# reLoaD_Motor.net
KiCad netlist of a schematic drawn in EAGLE
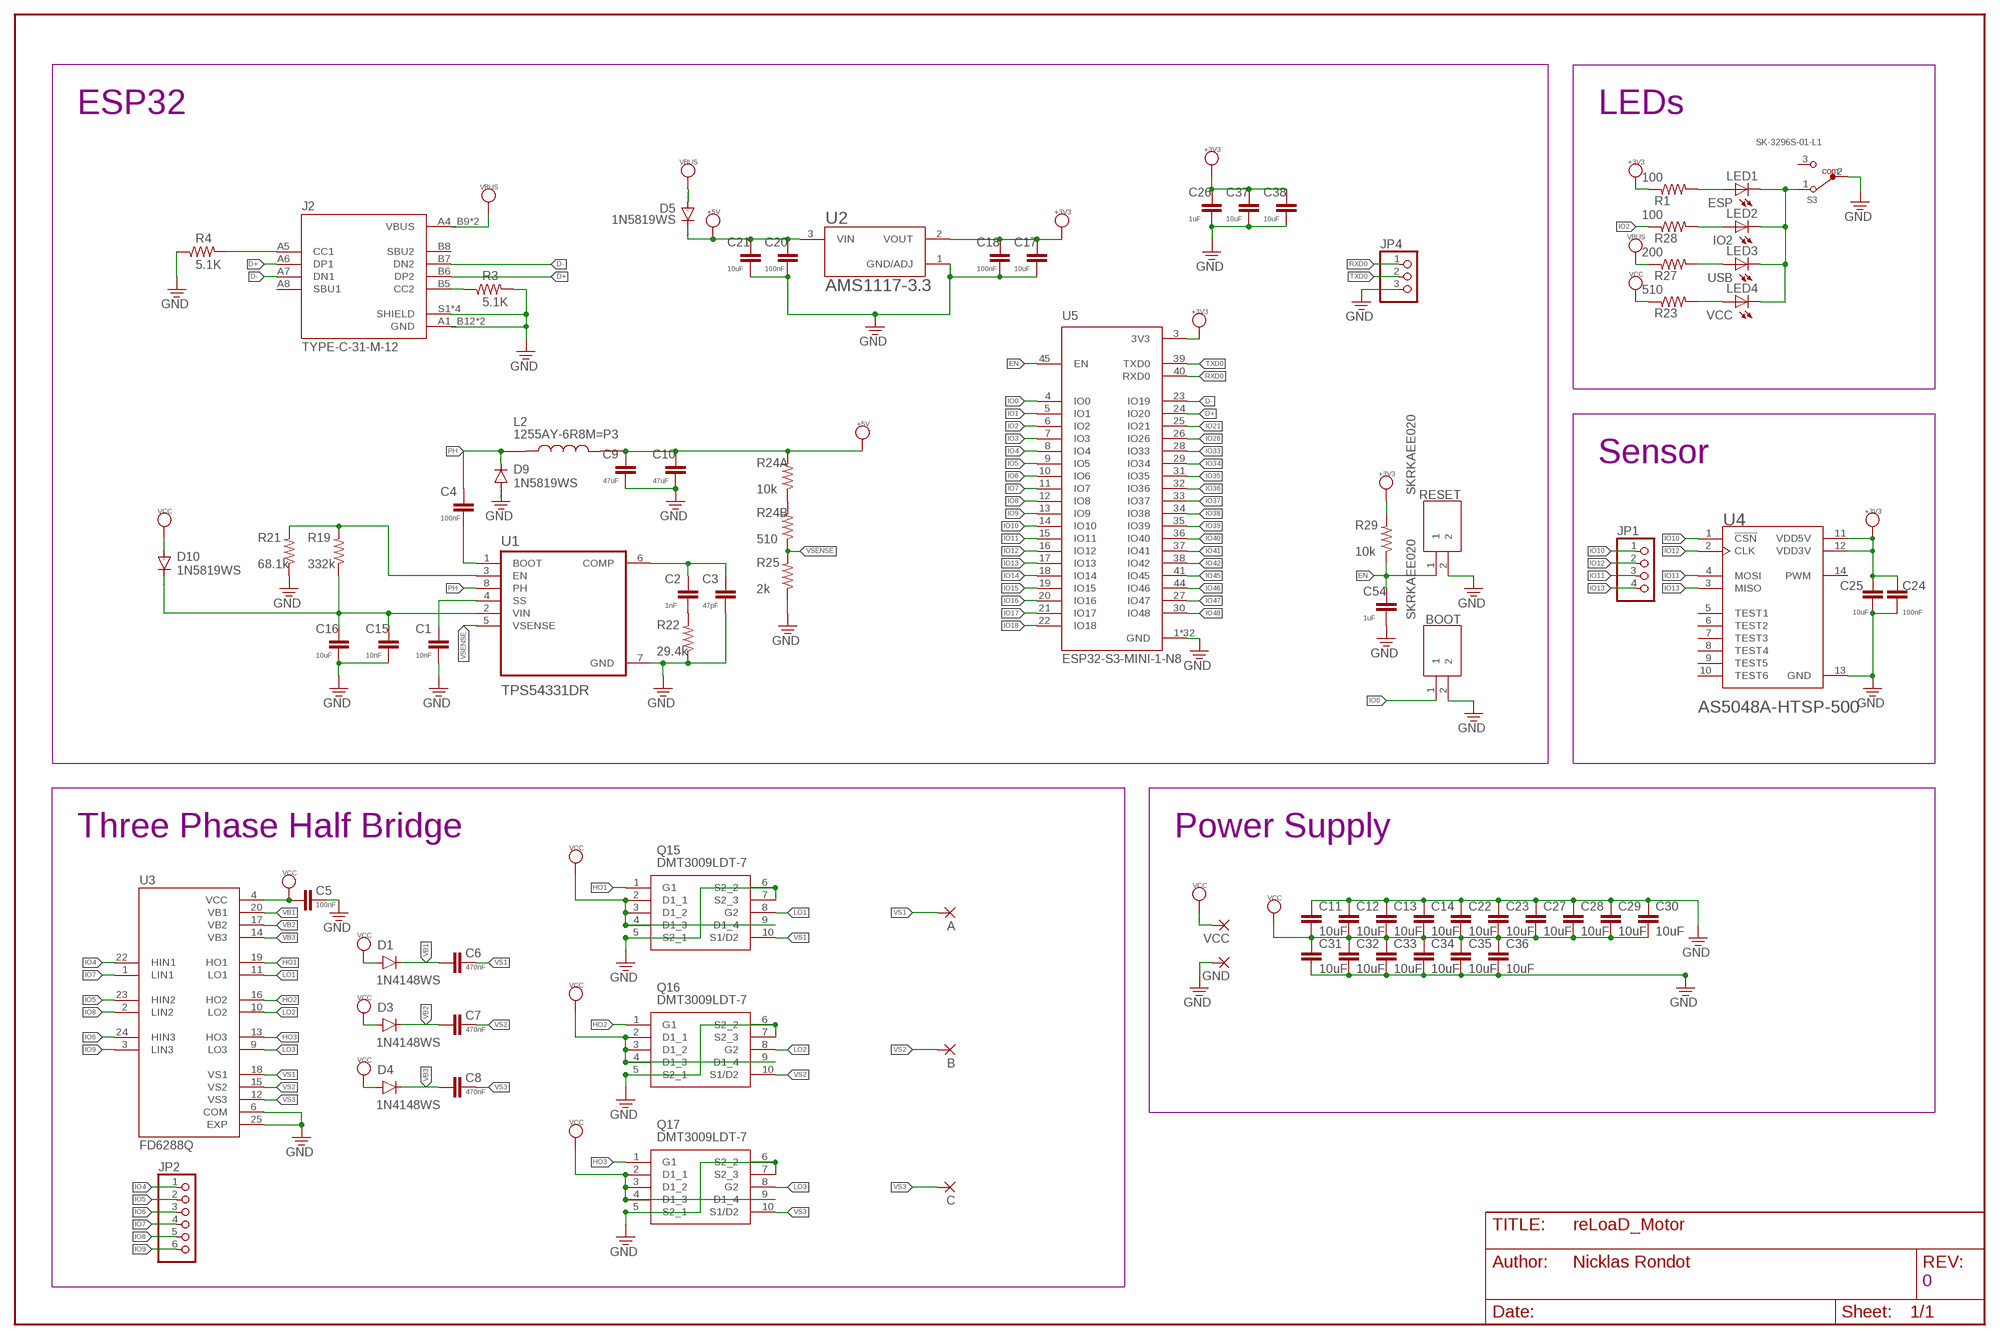
[diagram p0: schematic, sheet 1]

(export (version "E")
  (design (tool "Eeschema 10.0.6"))
  (components
    (comp (ref "A")
      (value "3,81/1,4")
      (footprint "eagle-import:3,81_1,4")
      (libsource (lib "eagle-import") (part "3,81/1,4"))
    )
    (comp (ref "B")
      (value "3,81/1,4")
      (footprint "eagle-import:3,81_1,4")
      (libsource (lib "eagle-import") (part "3,81/1,4"))
    )
    (comp (ref "BOOT")
      (value "SKRKAEE020")
      (footprint "eagle-import:SKRKAEE020")
      (fields (field (name "MOUSER_PART_NUMBER") "688-SKRKAEE020"))
      (libsource (lib "eagle-import") (part "SKRKAEE020"))
    )
    (comp (ref "C")
      (value "3,81/1,4")
      (footprint "eagle-import:3,81_1,4")
      (libsource (lib "eagle-import") (part "3,81/1,4"))
    )
    (comp (ref "C1")
      (value "10nF")
      (footprint "eagle-import:C0603K")
      (libsource (lib "eagle-import") (part "resistor_348_C-EUC0603K"))
    )
    (comp (ref "C2")
      (value "1nF")
      (footprint "eagle-import:C0603K")
      (libsource (lib "eagle-import") (part "resistor_348_C-EUC0603K"))
    )
    (comp (ref "C3")
      (value "47pF")
      (footprint "eagle-import:C0603K")
      (libsource (lib "eagle-import") (part "resistor_348_C-EUC0603K"))
    )
    (comp (ref "C4")
      (value "100nF")
      (footprint "eagle-import:C0603K")
      (libsource (lib "eagle-import") (part "resistor_348_C-EUC0603K"))
    )
    (comp (ref "C5")
      (value "100nF")
      (footprint "eagle-import:C0603K")
      (libsource (lib "eagle-import") (part "resistor_348_C-EUC0603K"))
    )
    (comp (ref "C6")
      (value "470nF")
      (footprint "eagle-import:C0603K")
      (libsource (lib "eagle-import") (part "resistor_348_C-EUC0603K"))
    )
    (comp (ref "C7")
      (value "470nF")
      (footprint "eagle-import:C0603K")
      (libsource (lib "eagle-import") (part "resistor_348_C-EUC0603K"))
    )
    (comp (ref "C8")
      (value "470nF")
      (footprint "eagle-import:C0603K")
      (libsource (lib "eagle-import") (part "resistor_348_C-EUC0603K"))
    )
    (comp (ref "C9")
      (value "47uF")
      (footprint "eagle-import:C0603K")
      (libsource (lib "eagle-import") (part "resistor_348_C-EUC0603K"))
    )
    (comp (ref "C10")
      (value "47uF")
      (footprint "eagle-import:C0603K")
      (libsource (lib "eagle-import") (part "resistor_348_C-EUC0603K"))
    )
    (comp (ref "C11")
      (value "10uF")
      (footprint "eagle-import:C0805K")
      (libsource (lib "eagle-import") (part "C-EUC0805K"))
    )
    (comp (ref "C12")
      (value "10uF")
      (footprint "eagle-import:C0805K")
      (libsource (lib "eagle-import") (part "C-EUC0805K"))
    )
    (comp (ref "C13")
      (value "10uF")
      (footprint "eagle-import:C0805K")
      (libsource (lib "eagle-import") (part "C-EUC0805K"))
    )
    (comp (ref "C14")
      (value "10uF")
      (footprint "eagle-import:C0805K")
      (libsource (lib "eagle-import") (part "C-EUC0805K"))
    )
    (comp (ref "C15")
      (value "10nF")
      (footprint "eagle-import:C0603K")
      (libsource (lib "eagle-import") (part "resistor_348_C-EUC0603K"))
    )
    (comp (ref "C16")
      (value "10uF")
      (footprint "eagle-import:C0603K")
      (libsource (lib "eagle-import") (part "resistor_348_C-EUC0603K"))
    )
    (comp (ref "C17")
      (value "10uF")
      (footprint "eagle-import:C0603K")
      (libsource (lib "eagle-import") (part "resistor_348_C-EUC0603K"))
    )
    (comp (ref "C18")
      (value "100nF")
      (footprint "eagle-import:C0603K")
      (libsource (lib "eagle-import") (part "resistor_348_C-EUC0603K"))
    )
    (comp (ref "C20")
      (value "100nF")
      (footprint "eagle-import:C0603K")
      (libsource (lib "eagle-import") (part "resistor_348_C-EUC0603K"))
    )
    (comp (ref "C21")
      (value "10uF")
      (footprint "eagle-import:C0603K")
      (libsource (lib "eagle-import") (part "resistor_348_C-EUC0603K"))
    )
    (comp (ref "C22")
      (value "10uF")
      (footprint "eagle-import:C0805K")
      (libsource (lib "eagle-import") (part "C-EUC0805K"))
    )
    (comp (ref "C23")
      (value "10uF")
      (footprint "eagle-import:C0805K")
      (libsource (lib "eagle-import") (part "C-EUC0805K"))
    )
    (comp (ref "C24")
      (value "100nF")
      (footprint "eagle-import:C0603K")
      (libsource (lib "eagle-import") (part "resistor_348_C-EUC0603K"))
    )
    (comp (ref "C25")
      (value "10uF")
      (footprint "eagle-import:C0603K")
      (libsource (lib "eagle-import") (part "resistor_348_C-EUC0603K"))
    )
    (comp (ref "C26")
      (value "1uF")
      (footprint "eagle-import:C0603K")
      (libsource (lib "eagle-import") (part "resistor_348_C-EUC0603K"))
    )
    (comp (ref "C27")
      (value "10uF")
      (footprint "eagle-import:C0805K")
      (libsource (lib "eagle-import") (part "C-EUC0805K"))
    )
    (comp (ref "C28")
      (value "10uF")
      (footprint "eagle-import:C0805K")
      (libsource (lib "eagle-import") (part "C-EUC0805K"))
    )
    (comp (ref "C29")
      (value "10uF")
      (footprint "eagle-import:C0805K")
      (libsource (lib "eagle-import") (part "C-EUC0805K"))
    )
    (comp (ref "C30")
      (value "10uF")
      (footprint "eagle-import:C0805K")
      (libsource (lib "eagle-import") (part "C-EUC0805K"))
    )
    (comp (ref "C31")
      (value "10uF")
      (footprint "eagle-import:C0805K")
      (libsource (lib "eagle-import") (part "C-EUC0805K"))
    )
    (comp (ref "C32")
      (value "10uF")
      (footprint "eagle-import:C0805K")
      (libsource (lib "eagle-import") (part "C-EUC0805K"))
    )
    (comp (ref "C33")
      (value "10uF")
      (footprint "eagle-import:C0805K")
      (libsource (lib "eagle-import") (part "C-EUC0805K"))
    )
    (comp (ref "C34")
      (value "10uF")
      (footprint "eagle-import:C0805K")
      (libsource (lib "eagle-import") (part "C-EUC0805K"))
    )
    (comp (ref "C35")
      (value "10uF")
      (footprint "eagle-import:C0805K")
      (libsource (lib "eagle-import") (part "C-EUC0805K"))
    )
    (comp (ref "C36")
      (value "10uF")
      (footprint "eagle-import:C0805K")
      (libsource (lib "eagle-import") (part "C-EUC0805K"))
    )
    (comp (ref "C37")
      (value "10uF")
      (footprint "eagle-import:C0603K")
      (libsource (lib "eagle-import") (part "resistor_348_C-EUC0603K"))
    )
    (comp (ref "C38")
      (value "10uF")
      (footprint "eagle-import:C0603K")
      (libsource (lib "eagle-import") (part "resistor_348_C-EUC0603K"))
    )
    (comp (ref "C54")
      (value "1uF")
      (footprint "eagle-import:C0603K")
      (libsource (lib "eagle-import") (part "resistor_348_C-EUC0603K"))
    )
    (comp (ref "D1")
      (value "1N4148WS")
      (footprint "eagle-import:SOD-323")
      (fields
        (field (name "DIGIKEY_PART_NUMBER") "1N4148WSFSTR-ND")
        (field (name "MANUFACTURER") "Diodes Incorporated")
        (field (name "CREATED_BY") "PCBLayout.com")
      )
      (libsource (lib "eagle-import") (part "1N4148WS"))
    )
    (comp (ref "D3")
      (value "1N4148WS")
      (footprint "eagle-import:SOD-323")
      (fields
        (field (name "DIGIKEY_PART_NUMBER") "1N4148WSFSTR-ND")
        (field (name "MANUFACTURER") "Diodes Incorporated")
        (field (name "CREATED_BY") "PCBLayout.com")
      )
      (libsource (lib "eagle-import") (part "1N4148WS"))
    )
    (comp (ref "D4")
      (value "1N4148WS")
      (footprint "eagle-import:SOD-323")
      (fields
        (field (name "DIGIKEY_PART_NUMBER") "1N4148WSFSTR-ND")
        (field (name "MANUFACTURER") "Diodes Incorporated")
        (field (name "CREATED_BY") "PCBLayout.com")
      )
      (libsource (lib "eagle-import") (part "1N4148WS"))
    )
    (comp (ref "D5")
      (value "1N5819WS")
      (footprint "eagle-import:SOD323-W")
      (libsource (lib "eagle-import") (part "DIODE-SOD323-W"))
    )
    (comp (ref "D9")
      (value "1N5819WS")
      (footprint "eagle-import:SOD323-W")
      (libsource (lib "eagle-import") (part "DIODE-SOD323-W"))
    )
    (comp (ref "D10")
      (value "1N5819WS")
      (footprint "eagle-import:SOD323-W")
      (libsource (lib "eagle-import") (part "DIODE-SOD323-W"))
    )
    (comp (ref "GND")
      (value "3,81/1,4")
      (footprint "eagle-import:3,81_1,4")
      (libsource (lib "eagle-import") (part "3,81/1,4"))
    )
    (comp (ref "J2")
      (value "TYPE-C-31-M-12")
      (footprint "eagle-import:HRO_TYPE-C-31-M-12")
      (fields (field (name "MF") "HRO Electronics Co., Ltd."))
      (libsource (lib "eagle-import") (part "TYPE-C-31-M-12"))
    )
    (comp (ref "JP1")
      (value "PINHD-1X4")
      (footprint "eagle-import:1X04")
      (libsource (lib "eagle-import") (part "PINHD-1X4"))
    )
    (comp (ref "JP2")
      (value "PINHD-1X6")
      (footprint "eagle-import:1X06")
      (libsource (lib "eagle-import") (part "PINHD-1X6"))
    )
    (comp (ref "JP4")
      (value "PINHD-1X3")
      (footprint "eagle-import:1X03")
      (libsource (lib "eagle-import") (part "PINHD-1X3"))
    )
    (comp (ref "L2")
      (value "1255AY-6R8M=P3")
      (footprint "eagle-import:IND_1255AY-6R8M=P3")
      (fields (field (name "MF") "Murata Electronics"))
      (libsource (lib "eagle-import") (part "1255AY-6R8M=P3"))
    )
    (comp (ref "LED1")
      (value "ESP")
      (footprint "eagle-import:CHIPLED_0805")
      (libsource (lib "eagle-import") (part "LEDCHIPLED_0805"))
    )
    (comp (ref "LED2")
      (value "IO2")
      (footprint "eagle-import:CHIPLED_0805")
      (libsource (lib "eagle-import") (part "LEDCHIPLED_0805"))
    )
    (comp (ref "LED3")
      (value "USB")
      (footprint "eagle-import:CHIPLED_0805")
      (libsource (lib "eagle-import") (part "LEDCHIPLED_0805"))
    )
    (comp (ref "LED4")
      (value "VCC")
      (footprint "eagle-import:CHIPLED_0805")
      (libsource (lib "eagle-import") (part "LEDCHIPLED_0805"))
    )
    (comp (ref "Q15")
      (value "DMT3009LDT-7")
      (footprint "eagle-import:DMT3009LDT7")
      (fields (field (name "MOUSER_PART_NUMBER") "621-DMT3009LDT-7"))
      (libsource (lib "eagle-import") (part "DMT3009LDT-7"))
    )
    (comp (ref "Q16")
      (value "DMT3009LDT-7")
      (footprint "eagle-import:DMT3009LDT7")
      (fields (field (name "MOUSER_PART_NUMBER") "621-DMT3009LDT-7"))
      (libsource (lib "eagle-import") (part "DMT3009LDT-7"))
    )
    (comp (ref "Q17")
      (value "DMT3009LDT-7")
      (footprint "eagle-import:DMT3009LDT7")
      (fields (field (name "MOUSER_PART_NUMBER") "621-DMT3009LDT-7"))
      (libsource (lib "eagle-import") (part "DMT3009LDT-7"))
    )
    (comp (ref "R1")
      (value "100")
      (footprint "eagle-import:R0603")
      (libsource (lib "eagle-import") (part "R-US_R0603"))
    )
    (comp (ref "R3")
      (value "5.1K")
      (footprint "eagle-import:R0603")
      (libsource (lib "eagle-import") (part "R-US_R0603"))
    )
    (comp (ref "R4")
      (value "5.1K")
      (footprint "eagle-import:R0603")
      (libsource (lib "eagle-import") (part "R-US_R0603"))
    )
    (comp (ref "R19")
      (value "332k")
      (footprint "eagle-import:R0603")
      (libsource (lib "eagle-import") (part "R-US_R0603"))
    )
    (comp (ref "R21")
      (value "68.1k")
      (footprint "eagle-import:R0603")
      (libsource (lib "eagle-import") (part "R-US_R0603"))
    )
    (comp (ref "R22")
      (value "29.4k")
      (footprint "eagle-import:R0603")
      (libsource (lib "eagle-import") (part "R-US_R0603"))
    )
    (comp (ref "R23")
      (value "510")
      (footprint "eagle-import:R0603")
      (libsource (lib "eagle-import") (part "R-US_R0603"))
    )
    (comp (ref "R24A")
      (value "10k")
      (footprint "eagle-import:R0603")
      (libsource (lib "eagle-import") (part "R-US_R0603"))
    )
    (comp (ref "R24B")
      (value "510")
      (footprint "eagle-import:R0603")
      (libsource (lib "eagle-import") (part "R-US_R0603"))
    )
    (comp (ref "R25")
      (value "2k")
      (footprint "eagle-import:R0603")
      (libsource (lib "eagle-import") (part "R-US_R0603"))
    )
    (comp (ref "R27")
      (value "200")
      (footprint "eagle-import:R0603")
      (libsource (lib "eagle-import") (part "R-US_R0603"))
    )
    (comp (ref "R28")
      (value "100")
      (footprint "eagle-import:R0603")
      (libsource (lib "eagle-import") (part "R-US_R0603"))
    )
    (comp (ref "R29")
      (value "10k")
      (footprint "eagle-import:R0603")
      (libsource (lib "eagle-import") (part "R-US_R0603"))
    )
    (comp (ref "RESET")
      (value "SKRKAEE020")
      (footprint "eagle-import:SKRKAEE020")
      (fields (field (name "MOUSER_PART_NUMBER") "688-SKRKAEE020"))
      (libsource (lib "eagle-import") (part "SKRKAEE020"))
    )
    (comp (ref "S3")
      (value "SK-3296S-01-L1")
      (footprint "eagle-import:450404015514")
      (libsource (lib "eagle-import") (part "450404015514"))
    )
    (comp (ref "U1")
      (value "TPS54331DR")
      (footprint "eagle-import:SOIC127P599X175-8N")
      (fields (field (name "MF") "Texas Instruments"))
      (libsource (lib "eagle-import") (part "TPS54331DR"))
    )
    (comp (ref "U2")
      (value "AMS1117-3.3")
      (footprint "eagle-import:SOT229P700X180-4N")
      (fields (field (name "MF") "Advanced Monolithic Systems"))
      (libsource (lib "eagle-import") (part "AMS1117-3.3"))
    )
    (comp (ref "U3")
      (value "FD6288Q")
      (footprint "eagle-import:QFN50P400X400X90-25N")
      (fields (field (name "MF") "Fortior Tech"))
      (libsource (lib "eagle-import") (part "FD6288Q"))
    )
    (comp (ref "U4")
      (value "AS5048A-HTSP-500")
      (footprint "eagle-import:SOP65P640X120-14N")
      (fields (field (name "MF") "ams"))
      (libsource (lib "eagle-import") (part "AS5048A-HTSP-500"))
    )
    (comp (ref "U5")
      (value "ESP32-S3-MINI-1-N8")
      (footprint "eagle-import:XCVR_ESP32-S3-MINI-1-N8")
      (fields (field (name "MF") "Espressif Systems"))
      (libsource (lib "eagle-import") (part "ESP32-S3-MINI-1-N8"))
    )
    (comp (ref "VCC")
      (value "3,81/1,4")
      (footprint "eagle-import:3,81_1,4")
      (libsource (lib "eagle-import") (part "3,81/1,4"))
    )
  )
  (nets
    (net (code "1") (name "+3V3") (class "Default")
      (node (ref "C17") (pin "1") (pinfunction "1_1") (pintype "passive"))
      (node (ref "C18") (pin "1") (pinfunction "1_1") (pintype "passive"))
      (node (ref "C24") (pin "2") (pinfunction "2_2") (pintype "passive"))
      (node (ref "C25") (pin "2") (pinfunction "2_2") (pintype "passive"))
      (node (ref "C26") (pin "1") (pinfunction "1_1") (pintype "passive"))
      (node (ref "C37") (pin "1") (pinfunction "1_1") (pintype "passive"))
      (node (ref "C38") (pin "1") (pinfunction "1_1") (pintype "passive"))
      (node (ref "R1") (pin "1") (pinfunction "1_1") (pintype "passive"))
      (node (ref "R29") (pin "2") (pinfunction "2_2") (pintype "passive"))
      (node (ref "U2") (pin "2") (pinfunction "VOUT_2") (pintype "output"))
      (node (ref "U4") (pin "11") (pinfunction "VDD5V_11") (pintype "power_in"))
      (node (ref "U4") (pin "12") (pinfunction "VDD3V_12") (pintype "power_in"))
      (node (ref "U5") (pin "3") (pinfunction "3V3_3") (pintype "power_in"))
    )
    (net (code "2") (name "+5V") (class "Default")
      (node (ref "C10") (pin "1") (pinfunction "1_1") (pintype "passive"))
      (node (ref "C20") (pin "1") (pinfunction "1_1") (pintype "passive"))
      (node (ref "C21") (pin "1") (pinfunction "1_1") (pintype "passive"))
      (node (ref "C9") (pin "1") (pinfunction "1_1") (pintype "passive"))
      (node (ref "D5") (pin "C") (pinfunction "C_C") (pintype "passive"))
      (node (ref "L2") (pin "2") (pinfunction "2_2") (pintype "passive"))
      (node (ref "R24A") (pin "2") (pinfunction "2_2") (pintype "passive"))
      (node (ref "U2") (pin "3") (pinfunction "VIN_3") (pintype "input"))
    )
    (net (code "3") (name "D+") (class "Default")
      (node (ref "J2") (pin "A6") (pinfunction "DP1_A6") (pintype "bidirectional"))
      (node (ref "J2") (pin "B6") (pinfunction "DP2_B6") (pintype "bidirectional"))
      (node (ref "U5") (pin "24") (pinfunction "IO20_24") (pintype "bidirectional"))
    )
    (net (code "4") (name "D-") (class "Default")
      (node (ref "J2") (pin "A7") (pinfunction "DN1_A7") (pintype "bidirectional"))
      (node (ref "J2") (pin "B7") (pinfunction "DN2_B7") (pintype "bidirectional"))
      (node (ref "U5") (pin "23") (pinfunction "IO19_23") (pintype "bidirectional"))
    )
    (net (code "5") (name "EN") (class "Default")
      (node (ref "C54") (pin "1") (pinfunction "1_1") (pintype "passive"))
      (node (ref "R29") (pin "1") (pinfunction "1_1") (pintype "passive"))
      (node (ref "RESET") (pin "1") (pinfunction "1_1") (pintype "bidirectional"))
      (node (ref "U5") (pin "45") (pinfunction "EN_45") (pintype "input"))
    )
    (net (code "6") (name "GND") (class "Default")
      (node (ref "BOOT") (pin "2") (pinfunction "2_2") (pintype "bidirectional"))
      (node (ref "C1") (pin "2") (pinfunction "2_2") (pintype "passive"))
      (node (ref "C10") (pin "2") (pinfunction "2_2") (pintype "passive"))
      (node (ref "C11") (pin "1") (pinfunction "1_1") (pintype "passive"))
      (node (ref "C12") (pin "1") (pinfunction "1_1") (pintype "passive"))
      (node (ref "C13") (pin "1") (pinfunction "1_1") (pintype "passive"))
      (node (ref "C14") (pin "1") (pinfunction "1_1") (pintype "passive"))
      (node (ref "C15") (pin "2") (pinfunction "2_2") (pintype "passive"))
      (node (ref "C16") (pin "2") (pinfunction "2_2") (pintype "passive"))
      (node (ref "C17") (pin "2") (pinfunction "2_2") (pintype "passive"))
      (node (ref "C18") (pin "2") (pinfunction "2_2") (pintype "passive"))
      (node (ref "C20") (pin "2") (pinfunction "2_2") (pintype "passive"))
      (node (ref "C21") (pin "2") (pinfunction "2_2") (pintype "passive"))
      (node (ref "C22") (pin "1") (pinfunction "1_1") (pintype "passive"))
      (node (ref "C23") (pin "1") (pinfunction "1_1") (pintype "passive"))
      (node (ref "C24") (pin "1") (pinfunction "1_1") (pintype "passive"))
      (node (ref "C25") (pin "1") (pinfunction "1_1") (pintype "passive"))
      (node (ref "C26") (pin "2") (pinfunction "2_2") (pintype "passive"))
      (node (ref "C27") (pin "1") (pinfunction "1_1") (pintype "passive"))
      (node (ref "C28") (pin "1") (pinfunction "1_1") (pintype "passive"))
      (node (ref "C29") (pin "1") (pinfunction "1_1") (pintype "passive"))
      (node (ref "C3") (pin "2") (pinfunction "2_2") (pintype "passive"))
      (node (ref "C30") (pin "1") (pinfunction "1_1") (pintype "passive"))
      (node (ref "C31") (pin "2") (pinfunction "2_2") (pintype "passive"))
      (node (ref "C32") (pin "2") (pinfunction "2_2") (pintype "passive"))
      (node (ref "C33") (pin "2") (pinfunction "2_2") (pintype "passive"))
      (node (ref "C34") (pin "2") (pinfunction "2_2") (pintype "passive"))
      (node (ref "C35") (pin "2") (pinfunction "2_2") (pintype "passive"))
      (node (ref "C36") (pin "2") (pinfunction "2_2") (pintype "passive"))
      (node (ref "C37") (pin "2") (pinfunction "2_2") (pintype "passive"))
      (node (ref "C38") (pin "2") (pinfunction "2_2") (pintype "passive"))
      (node (ref "C5") (pin "1") (pinfunction "1_1") (pintype "passive"))
      (node (ref "C54") (pin "2") (pinfunction "2_2") (pintype "passive"))
      (node (ref "C9") (pin "2") (pinfunction "2_2") (pintype "passive"))
      (node (ref "D9") (pin "A") (pinfunction "A_A") (pintype "passive"))
      (node (ref "GND") (pin "1") (pinfunction "P_1") (pintype "passive"))
      (node (ref "J2") (pin "A1_B12") (pinfunction "GND_A1_B12") (pintype "power_in"))
      (node (ref "J2") (pin "B1_A12") (pinfunction "GND_B1_A12") (pintype "power_in"))
      (node (ref "J2") (pin "S1") (pinfunction "SHIELD_S1") (pintype "passive"))
      (node (ref "J2") (pin "S2") (pinfunction "SHIELD_S2") (pintype "passive"))
      (node (ref "J2") (pin "S3") (pinfunction "SHIELD_S3") (pintype "passive"))
      (node (ref "J2") (pin "S4") (pinfunction "SHIELD_S4") (pintype "passive"))
      (node (ref "JP4") (pin "3") (pinfunction "3_3") (pintype "passive"))
      (node (ref "Q15") (pin "5") (pinfunction "S2_1_5") (pintype "bidirectional"))
      (node (ref "Q15") (pin "6") (pinfunction "S2_2_6") (pintype "bidirectional"))
      (node (ref "Q15") (pin "7") (pinfunction "S2_3_7") (pintype "bidirectional"))
      (node (ref "Q16") (pin "5") (pinfunction "S2_1_5") (pintype "bidirectional"))
      (node (ref "Q16") (pin "6") (pinfunction "S2_2_6") (pintype "bidirectional"))
      (node (ref "Q16") (pin "7") (pinfunction "S2_3_7") (pintype "bidirectional"))
      (node (ref "Q17") (pin "5") (pinfunction "S2_1_5") (pintype "bidirectional"))
      (node (ref "Q17") (pin "6") (pinfunction "S2_2_6") (pintype "bidirectional"))
      (node (ref "Q17") (pin "7") (pinfunction "S2_3_7") (pintype "bidirectional"))
      (node (ref "R21") (pin "1") (pinfunction "1_1") (pintype "passive"))
      (node (ref "R22") (pin "1") (pinfunction "1_1") (pintype "passive"))
      (node (ref "R25") (pin "1") (pinfunction "1_1") (pintype "passive"))
      (node (ref "R3") (pin "2") (pinfunction "2_2") (pintype "passive"))
      (node (ref "R4") (pin "1") (pinfunction "1_1") (pintype "passive"))
      (node (ref "RESET") (pin "2") (pinfunction "2_2") (pintype "bidirectional"))
      (node (ref "S3") (pin "2") (pinfunction "2_2") (pintype "passive"))
      (node (ref "U1") (pin "7") (pinfunction "GND_7") (pintype "power_in"))
      (node (ref "U2") (pin "1") (pinfunction "GND/ADJ_1") (pintype "power_in"))
      (node (ref "U3") (pin "25") (pinfunction "EXP_25") (pintype "power_in"))
      (node (ref "U3") (pin "6") (pinfunction "COM_6") (pintype "power_in"))
      (node (ref "U4") (pin "13") (pinfunction "GND_13") (pintype "passive"))
      (node (ref "U5") (pin "1") (pinfunction "GND_1") (pintype "power_in"))
      (node (ref "U5") (pin "2") (pinfunction "GND_2") (pintype "power_in"))
      (node (ref "U5") (pin "42") (pinfunction "GND_42") (pintype "power_in"))
      (node (ref "U5") (pin "43") (pinfunction "GND_43") (pintype "power_in"))
      (node (ref "U5") (pin "46") (pinfunction "GND_46") (pintype "power_in"))
      (node (ref "U5") (pin "47") (pinfunction "GND_47") (pintype "power_in"))
      (node (ref "U5") (pin "48") (pinfunction "GND_48") (pintype "power_in"))
      (node (ref "U5") (pin "49") (pinfunction "GND_49") (pintype "power_in"))
      (node (ref "U5") (pin "50") (pinfunction "GND_50") (pintype "power_in"))
      (node (ref "U5") (pin "51") (pinfunction "GND_51") (pintype "power_in"))
      (node (ref "U5") (pin "52") (pinfunction "GND_52") (pintype "power_in"))
      (node (ref "U5") (pin "53") (pinfunction "GND_53") (pintype "power_in"))
      (node (ref "U5") (pin "54") (pinfunction "GND_54") (pintype "power_in"))
      (node (ref "U5") (pin "55") (pinfunction "GND_55") (pintype "power_in"))
      (node (ref "U5") (pin "56") (pinfunction "GND_56") (pintype "power_in"))
      (node (ref "U5") (pin "57") (pinfunction "GND_57") (pintype "power_in"))
      (node (ref "U5") (pin "58") (pinfunction "GND_58") (pintype "power_in"))
      (node (ref "U5") (pin "59") (pinfunction "GND_59") (pintype "power_in"))
      (node (ref "U5") (pin "60") (pinfunction "GND_60") (pintype "power_in"))
      (node (ref "U5") (pin "61") (pinfunction "GND_61") (pintype "power_in"))
      (node (ref "U5") (pin "61_1") (pinfunction "GND_61_1") (pintype "power_in"))
      (node (ref "U5") (pin "61_2") (pinfunction "GND_61_2") (pintype "power_in"))
      (node (ref "U5") (pin "61_3") (pinfunction "GND_61_3") (pintype "power_in"))
      (node (ref "U5") (pin "61_4") (pinfunction "GND_61_4") (pintype "power_in"))
      (node (ref "U5") (pin "61_5") (pinfunction "GND_61_5") (pintype "power_in"))
      (node (ref "U5") (pin "61_6") (pinfunction "GND_61_6") (pintype "power_in"))
      (node (ref "U5") (pin "61_7") (pinfunction "GND_61_7") (pintype "power_in"))
      (node (ref "U5") (pin "61_8") (pinfunction "GND_61_8") (pintype "power_in"))
      (node (ref "U5") (pin "62") (pinfunction "GND_62") (pintype "power_in"))
      (node (ref "U5") (pin "63") (pinfunction "GND_63") (pintype "power_in"))
      (node (ref "U5") (pin "64") (pinfunction "GND_64") (pintype "power_in"))
      (node (ref "U5") (pin "65") (pinfunction "GND_65") (pintype "power_in"))
    )
    (net (code "7") (name "HO1") (class "Default")
      (node (ref "Q15") (pin "1") (pinfunction "G1_1") (pintype "bidirectional"))
      (node (ref "U3") (pin "19") (pinfunction "HO1_19") (pintype "output"))
    )
    (net (code "8") (name "HO2") (class "Default")
      (node (ref "Q16") (pin "1") (pinfunction "G1_1") (pintype "bidirectional"))
      (node (ref "U3") (pin "16") (pinfunction "HO2_16") (pintype "output"))
    )
    (net (code "9") (name "HO3") (class "Default")
      (node (ref "Q17") (pin "1") (pinfunction "G1_1") (pintype "bidirectional"))
      (node (ref "U3") (pin "13") (pinfunction "HO3_13") (pintype "output"))
    )
    (net (code "10") (name "IO0") (class "Default")
      (node (ref "BOOT") (pin "1") (pinfunction "1_1") (pintype "bidirectional"))
      (node (ref "U5") (pin "4") (pinfunction "IO0_4") (pintype "bidirectional"))
    )
    (net (code "11") (name "IO1") (class "Default")
      (node (ref "U5") (pin "5") (pinfunction "IO1_5") (pintype "bidirectional"))
    )
    (net (code "12") (name "IO2") (class "Default")
      (node (ref "R28") (pin "1") (pinfunction "1_1") (pintype "passive"))
      (node (ref "U5") (pin "6") (pinfunction "IO2_6") (pintype "bidirectional"))
    )
    (net (code "13") (name "IO3") (class "Default")
      (node (ref "U5") (pin "7") (pinfunction "IO3_7") (pintype "bidirectional"))
    )
    (net (code "14") (name "IO4") (class "Default")
      (node (ref "JP2") (pin "1") (pinfunction "1_1") (pintype "passive"))
      (node (ref "U3") (pin "22") (pinfunction "HIN1_22") (pintype "input"))
      (node (ref "U5") (pin "8") (pinfunction "IO4_8") (pintype "bidirectional"))
    )
    (net (code "15") (name "IO5") (class "Default")
      (node (ref "JP2") (pin "2") (pinfunction "2_2") (pintype "passive"))
      (node (ref "U3") (pin "23") (pinfunction "HIN2_23") (pintype "input"))
      (node (ref "U5") (pin "9") (pinfunction "IO5_9") (pintype "bidirectional"))
    )
    (net (code "16") (name "IO6") (class "Default")
      (node (ref "JP2") (pin "3") (pinfunction "3_3") (pintype "passive"))
      (node (ref "U3") (pin "24") (pinfunction "HIN3_24") (pintype "input"))
      (node (ref "U5") (pin "10") (pinfunction "IO6_10") (pintype "bidirectional"))
    )
    (net (code "17") (name "IO7") (class "Default")
      (node (ref "JP2") (pin "4") (pinfunction "4_4") (pintype "passive"))
      (node (ref "U3") (pin "1") (pinfunction "LIN1_1") (pintype "input"))
      (node (ref "U5") (pin "11") (pinfunction "IO7_11") (pintype "bidirectional"))
    )
    (net (code "18") (name "IO8") (class "Default")
      (node (ref "JP2") (pin "5") (pinfunction "5_5") (pintype "passive"))
      (node (ref "U3") (pin "2") (pinfunction "LIN2_2") (pintype "input"))
      (node (ref "U5") (pin "12") (pinfunction "IO8_12") (pintype "bidirectional"))
    )
    (net (code "19") (name "IO9") (class "Default")
      (node (ref "JP2") (pin "6") (pinfunction "6_6") (pintype "passive"))
      (node (ref "U3") (pin "3") (pinfunction "LIN3_3") (pintype "input"))
      (node (ref "U5") (pin "13") (pinfunction "IO9_13") (pintype "bidirectional"))
    )
    (net (code "20") (name "IO10") (class "Default")
      (node (ref "JP1") (pin "1") (pinfunction "1_1") (pintype "passive"))
      (node (ref "U4") (pin "1") (pinfunction "~{CSN}_1") (pintype "input"))
      (node (ref "U5") (pin "14") (pinfunction "IO10_14") (pintype "bidirectional"))
    )
    (net (code "21") (name "IO11") (class "Default")
      (node (ref "JP1") (pin "3") (pinfunction "3_3") (pintype "passive"))
      (node (ref "U4") (pin "4") (pinfunction "MOSI_4") (pintype "input"))
      (node (ref "U5") (pin "15") (pinfunction "IO11_15") (pintype "bidirectional"))
    )
    (net (code "22") (name "IO12") (class "Default")
      (node (ref "JP1") (pin "2") (pinfunction "2_2") (pintype "passive"))
      (node (ref "U4") (pin "2") (pinfunction "CLK_2") (pintype "input"))
      (node (ref "U5") (pin "16") (pinfunction "IO12_16") (pintype "bidirectional"))
    )
    (net (code "23") (name "IO13") (class "Default")
      (node (ref "JP1") (pin "4") (pinfunction "4_4") (pintype "passive"))
      (node (ref "U4") (pin "3") (pinfunction "MISO_3") (pintype "bidirectional"))
      (node (ref "U5") (pin "17") (pinfunction "IO13_17") (pintype "bidirectional"))
    )
    (net (code "24") (name "IO14") (class "Default")
      (node (ref "U5") (pin "18") (pinfunction "IO14_18") (pintype "bidirectional"))
    )
    (net (code "25") (name "IO15") (class "Default")
      (node (ref "U5") (pin "19") (pinfunction "IO15_19") (pintype "bidirectional"))
    )
    (net (code "26") (name "IO16") (class "Default")
      (node (ref "U5") (pin "20") (pinfunction "IO16_20") (pintype "bidirectional"))
    )
    (net (code "27") (name "IO17") (class "Default")
      (node (ref "U5") (pin "21") (pinfunction "IO17_21") (pintype "bidirectional"))
    )
    (net (code "28") (name "IO18") (class "Default")
      (node (ref "U5") (pin "22") (pinfunction "IO18_22") (pintype "bidirectional"))
    )
    (net (code "29") (name "IO21") (class "Default")
      (node (ref "U5") (pin "25") (pinfunction "IO21_25") (pintype "bidirectional"))
    )
    (net (code "30") (name "IO26") (class "Default")
      (node (ref "U5") (pin "26") (pinfunction "IO26_26") (pintype "bidirectional"))
    )
    (net (code "31") (name "IO33") (class "Default")
      (node (ref "U5") (pin "28") (pinfunction "IO33_28") (pintype "bidirectional"))
    )
    (net (code "32") (name "IO34") (class "Default")
      (node (ref "U5") (pin "29") (pinfunction "IO34_29") (pintype "bidirectional"))
    )
    (net (code "33") (name "IO35") (class "Default")
      (node (ref "U5") (pin "31") (pinfunction "IO35_31") (pintype "bidirectional"))
    )
    (net (code "34") (name "IO36") (class "Default")
      (node (ref "U5") (pin "32") (pinfunction "IO36_32") (pintype "bidirectional"))
    )
    (net (code "35") (name "IO37") (class "Default")
      (node (ref "U5") (pin "33") (pinfunction "IO37_33") (pintype "bidirectional"))
    )
    (net (code "36") (name "IO38") (class "Default")
      (node (ref "U5") (pin "34") (pinfunction "IO38_34") (pintype "bidirectional"))
    )
    (net (code "37") (name "IO39") (class "Default")
      (node (ref "U5") (pin "35") (pinfunction "IO39_35") (pintype "bidirectional"))
    )
    (net (code "38") (name "IO40") (class "Default")
      (node (ref "U5") (pin "36") (pinfunction "IO40_36") (pintype "bidirectional"))
    )
    (net (code "39") (name "IO41") (class "Default")
      (node (ref "U5") (pin "37") (pinfunction "IO41_37") (pintype "bidirectional"))
    )
    (net (code "40") (name "IO42") (class "Default")
      (node (ref "U5") (pin "38") (pinfunction "IO42_38") (pintype "bidirectional"))
    )
    (net (code "41") (name "IO45") (class "Default")
      (node (ref "U5") (pin "41") (pinfunction "IO45_41") (pintype "bidirectional"))
    )
    (net (code "42") (name "IO46") (class "Default")
      (node (ref "U5") (pin "44") (pinfunction "IO46_44") (pintype "bidirectional"))
    )
    (net (code "43") (name "IO47") (class "Default")
      (node (ref "U5") (pin "27") (pinfunction "IO47_27") (pintype "bidirectional"))
    )
    (net (code "44") (name "IO48") (class "Default")
      (node (ref "U5") (pin "30") (pinfunction "IO48_30") (pintype "bidirectional"))
    )
    (net (code "45") (name "LO1") (class "Default")
      (node (ref "Q15") (pin "8") (pinfunction "G2_8") (pintype "bidirectional"))
      (node (ref "U3") (pin "11") (pinfunction "LO1_11") (pintype "output"))
    )
    (net (code "46") (name "LO2") (class "Default")
      (node (ref "Q16") (pin "8") (pinfunction "G2_8") (pintype "bidirectional"))
      (node (ref "U3") (pin "10") (pinfunction "LO2_10") (pintype "output"))
    )
    (net (code "47") (name "LO3") (class "Default")
      (node (ref "Q17") (pin "8") (pinfunction "G2_8") (pintype "bidirectional"))
      (node (ref "U3") (pin "9") (pinfunction "LO3_9") (pintype "output"))
    )
    (net (code "48") (name "Net-(C2-Pad2)") (class "Default")
      (node (ref "C2") (pin "2") (pinfunction "2_2") (pintype "passive"))
      (node (ref "R22") (pin "2") (pinfunction "2_2") (pintype "passive"))
    )
    (net (code "49") (name "Net-(J2-CC1)") (class "Default")
      (node (ref "J2") (pin "A5") (pinfunction "CC1_A5") (pintype "bidirectional"))
      (node (ref "R4") (pin "2") (pinfunction "2_2") (pintype "passive"))
    )
    (net (code "50") (name "Net-(J2-CC2)") (class "Default")
      (node (ref "J2") (pin "B5") (pinfunction "CC2_B5") (pintype "bidirectional"))
      (node (ref "R3") (pin "1") (pinfunction "1_1") (pintype "passive"))
    )
    (net (code "51") (name "Net-(LED1-PadA)") (class "Default")
      (node (ref "LED1") (pin "A") (pinfunction "A_A") (pintype "passive"))
      (node (ref "R1") (pin "2") (pinfunction "2_2") (pintype "passive"))
    )
    (net (code "52") (name "Net-(LED1-PadC)") (class "Default")
      (node (ref "LED1") (pin "C") (pinfunction "C_C") (pintype "passive"))
      (node (ref "LED2") (pin "C") (pinfunction "C_C") (pintype "passive"))
      (node (ref "LED3") (pin "C") (pinfunction "C_C") (pintype "passive"))
      (node (ref "LED4") (pin "C") (pinfunction "C_C") (pintype "passive"))
      (node (ref "S3") (pin "1") (pinfunction "1_1") (pintype "passive"))
    )
    (net (code "53") (name "Net-(LED2-PadA)") (class "Default")
      (node (ref "LED2") (pin "A") (pinfunction "A_A") (pintype "passive"))
      (node (ref "R28") (pin "2") (pinfunction "2_2") (pintype "passive"))
    )
    (net (code "54") (name "Net-(LED3-PadA)") (class "Default")
      (node (ref "LED3") (pin "A") (pinfunction "A_A") (pintype "passive"))
      (node (ref "R27") (pin "2") (pinfunction "2_2") (pintype "passive"))
    )
    (net (code "55") (name "Net-(LED4-PadA)") (class "Default")
      (node (ref "LED4") (pin "A") (pinfunction "A_A") (pintype "passive"))
      (node (ref "R23") (pin "2") (pinfunction "2_2") (pintype "passive"))
    )
    (net (code "56") (name "Net-(R24A-Pad1)") (class "Default")
      (node (ref "R24A") (pin "1") (pinfunction "1_1") (pintype "passive"))
      (node (ref "R24B") (pin "2") (pinfunction "2_2") (pintype "passive"))
    )
    (net (code "57") (name "Net-(U1-BOOT)") (class "Default")
      (node (ref "C4") (pin "2") (pinfunction "2_2") (pintype "passive"))
      (node (ref "U1") (pin "1") (pinfunction "BOOT_1") (pintype "input"))
    )
    (net (code "58") (name "Net-(U1-COMP)") (class "Default")
      (node (ref "C2") (pin "1") (pinfunction "1_1") (pintype "passive"))
      (node (ref "C3") (pin "1") (pinfunction "1_1") (pintype "passive"))
      (node (ref "U1") (pin "6") (pinfunction "COMP_6") (pintype "output"))
    )
    (net (code "59") (name "Net-(U1-EN)") (class "Default")
      (node (ref "R19") (pin "2") (pinfunction "2_2") (pintype "passive"))
      (node (ref "R21") (pin "2") (pinfunction "2_2") (pintype "passive"))
      (node (ref "U1") (pin "3") (pinfunction "EN_3") (pintype "input"))
    )
    (net (code "60") (name "Net-(U1-SS)") (class "Default")
      (node (ref "C1") (pin "1") (pinfunction "1_1") (pintype "passive"))
      (node (ref "U1") (pin "4") (pinfunction "SS_4") (pintype "input"))
    )
    (net (code "61") (name "Net-(U1-VIN)") (class "Default")
      (node (ref "C15") (pin "1") (pinfunction "1_1") (pintype "passive"))
      (node (ref "C16") (pin "1") (pinfunction "1_1") (pintype "passive"))
      (node (ref "D10") (pin "C") (pinfunction "C_C") (pintype "passive"))
      (node (ref "R19") (pin "1") (pinfunction "1_1") (pintype "passive"))
      (node (ref "U1") (pin "2") (pinfunction "VIN_2") (pintype "input"))
    )
    (net (code "62") (name "PH") (class "Default")
      (node (ref "C4") (pin "1") (pinfunction "1_1") (pintype "passive"))
      (node (ref "D9") (pin "C") (pinfunction "C_C") (pintype "passive"))
      (node (ref "L2") (pin "1") (pinfunction "1_1") (pintype "passive"))
      (node (ref "U1") (pin "8") (pinfunction "PH_8") (pintype "input"))
    )
    (net (code "63") (name "RXD0") (class "Default")
      (node (ref "JP4") (pin "1") (pinfunction "1_1") (pintype "passive"))
      (node (ref "U5") (pin "40") (pinfunction "RXD0_40") (pintype "bidirectional"))
    )
    (net (code "64") (name "TXD0") (class "Default")
      (node (ref "JP4") (pin "2") (pinfunction "2_2") (pintype "passive"))
      (node (ref "U5") (pin "39") (pinfunction "TXD0_39") (pintype "bidirectional"))
    )
    (net (code "65") (name "VB1") (class "Default")
      (node (ref "C6") (pin "1") (pinfunction "1_1") (pintype "passive"))
      (node (ref "D1") (pin "C") (pinfunction "C_C") (pintype "passive"))
      (node (ref "U3") (pin "20") (pinfunction "VB1_20") (pintype "power_in"))
    )
    (net (code "66") (name "VB2") (class "Default")
      (node (ref "C7") (pin "1") (pinfunction "1_1") (pintype "passive"))
      (node (ref "D3") (pin "C") (pinfunction "C_C") (pintype "passive"))
      (node (ref "U3") (pin "17") (pinfunction "VB2_17") (pintype "power_in"))
    )
    (net (code "67") (name "VB3") (class "Default")
      (node (ref "C8") (pin "1") (pinfunction "1_1") (pintype "passive"))
      (node (ref "D4") (pin "C") (pinfunction "C_C") (pintype "passive"))
      (node (ref "U3") (pin "14") (pinfunction "VB3_14") (pintype "power_in"))
    )
    (net (code "68") (name "VBUS") (class "Default")
      (node (ref "D5") (pin "A") (pinfunction "A_A") (pintype "passive"))
      (node (ref "J2") (pin "A4_B9") (pinfunction "VBUS_A4_B9") (pintype "power_in"))
      (node (ref "J2") (pin "B4_A9") (pinfunction "VBUS_B4_A9") (pintype "power_in"))
      (node (ref "R27") (pin "1") (pinfunction "1_1") (pintype "passive"))
    )
    (net (code "69") (name "VCC") (class "Default")
      (node (ref "C11") (pin "2") (pinfunction "2_2") (pintype "passive"))
      (node (ref "C12") (pin "2") (pinfunction "2_2") (pintype "passive"))
      (node (ref "C13") (pin "2") (pinfunction "2_2") (pintype "passive"))
      (node (ref "C14") (pin "2") (pinfunction "2_2") (pintype "passive"))
      (node (ref "C22") (pin "2") (pinfunction "2_2") (pintype "passive"))
      (node (ref "C23") (pin "2") (pinfunction "2_2") (pintype "passive"))
      (node (ref "C27") (pin "2") (pinfunction "2_2") (pintype "passive"))
      (node (ref "C28") (pin "2") (pinfunction "2_2") (pintype "passive"))
      (node (ref "C29") (pin "2") (pinfunction "2_2") (pintype "passive"))
      (node (ref "C30") (pin "2") (pinfunction "2_2") (pintype "passive"))
      (node (ref "C31") (pin "1") (pinfunction "1_1") (pintype "passive"))
      (node (ref "C32") (pin "1") (pinfunction "1_1") (pintype "passive"))
      (node (ref "C33") (pin "1") (pinfunction "1_1") (pintype "passive"))
      (node (ref "C34") (pin "1") (pinfunction "1_1") (pintype "passive"))
      (node (ref "C35") (pin "1") (pinfunction "1_1") (pintype "passive"))
      (node (ref "C36") (pin "1") (pinfunction "1_1") (pintype "passive"))
      (node (ref "C5") (pin "2") (pinfunction "2_2") (pintype "passive"))
      (node (ref "D1") (pin "A") (pinfunction "A_A") (pintype "passive"))
      (node (ref "D10") (pin "A") (pinfunction "A_A") (pintype "passive"))
      (node (ref "D3") (pin "A") (pinfunction "A_A") (pintype "passive"))
      (node (ref "D4") (pin "A") (pinfunction "A_A") (pintype "passive"))
      (node (ref "Q15") (pin "2") (pinfunction "D1_1_2") (pintype "bidirectional"))
      (node (ref "Q15") (pin "3") (pinfunction "D1_2_3") (pintype "bidirectional"))
      (node (ref "Q15") (pin "4") (pinfunction "D1_3_4") (pintype "bidirectional"))
      (node (ref "Q15") (pin "9") (pinfunction "D1_4_9") (pintype "bidirectional"))
      (node (ref "Q16") (pin "2") (pinfunction "D1_1_2") (pintype "bidirectional"))
      (node (ref "Q16") (pin "3") (pinfunction "D1_2_3") (pintype "bidirectional"))
      (node (ref "Q16") (pin "4") (pinfunction "D1_3_4") (pintype "bidirectional"))
      (node (ref "Q16") (pin "9") (pinfunction "D1_4_9") (pintype "bidirectional"))
      (node (ref "Q17") (pin "2") (pinfunction "D1_1_2") (pintype "bidirectional"))
      (node (ref "Q17") (pin "3") (pinfunction "D1_2_3") (pintype "bidirectional"))
      (node (ref "Q17") (pin "4") (pinfunction "D1_3_4") (pintype "bidirectional"))
      (node (ref "Q17") (pin "9") (pinfunction "D1_4_9") (pintype "bidirectional"))
      (node (ref "R23") (pin "1") (pinfunction "1_1") (pintype "passive"))
      (node (ref "U3") (pin "4") (pinfunction "VCC_4") (pintype "power_in"))
      (node (ref "VCC") (pin "1") (pinfunction "P_1") (pintype "passive"))
    )
    (net (code "70") (name "VS1") (class "Default")
      (node (ref "A") (pin "1") (pinfunction "P_1") (pintype "passive"))
      (node (ref "C6") (pin "2") (pinfunction "2_2") (pintype "passive"))
      (node (ref "Q15") (pin "10") (pinfunction "S1/D2_10") (pintype "bidirectional"))
      (node (ref "U3") (pin "18") (pinfunction "VS1_18") (pintype "power_in"))
    )
    (net (code "71") (name "VS2") (class "Default")
      (node (ref "B") (pin "1") (pinfunction "P_1") (pintype "passive"))
      (node (ref "C7") (pin "2") (pinfunction "2_2") (pintype "passive"))
      (node (ref "Q16") (pin "10") (pinfunction "S1/D2_10") (pintype "bidirectional"))
      (node (ref "U3") (pin "15") (pinfunction "VS2_15") (pintype "power_in"))
    )
    (net (code "72") (name "VS3") (class "Default")
      (node (ref "C") (pin "1") (pinfunction "P_1") (pintype "passive"))
      (node (ref "C8") (pin "2") (pinfunction "2_2") (pintype "passive"))
      (node (ref "Q17") (pin "10") (pinfunction "S1/D2_10") (pintype "bidirectional"))
      (node (ref "U3") (pin "12") (pinfunction "VS3_12") (pintype "power_in"))
    )
    (net (code "73") (name "VSENSE") (class "Default")
      (node (ref "R24B") (pin "1") (pinfunction "1_1") (pintype "passive"))
      (node (ref "R25") (pin "2") (pinfunction "2_2") (pintype "passive"))
      (node (ref "U1") (pin "5") (pinfunction "VSENSE_5") (pintype "input"))
    )
    (net (code "74") (name "unconnected-(J2-SBU1-PadA8)") (class "Default")
      (node (ref "J2") (pin "A8") (pinfunction "SBU1_A8") (pintype "bidirectional"))
    )
    (net (code "75") (name "unconnected-(J2-SBU2-PadB8)") (class "Default")
      (node (ref "J2") (pin "B8") (pinfunction "SBU2_B8") (pintype "bidirectional"))
    )
    (net (code "76") (name "unconnected-(S3-Pad3)") (class "Default")
      (node (ref "S3") (pin "3") (pinfunction "3_3") (pintype "passive"))
    )
    (net (code "77") (name "unconnected-(U4-PWM-Pad14)") (class "Default")
      (node (ref "U4") (pin "14") (pinfunction "PWM_14") (pintype "output"))
    )
    (net (code "78") (name "unconnected-(U4-TEST1-Pad5)") (class "Default")
      (node (ref "U4") (pin "5") (pinfunction "TEST1_5") (pintype "bidirectional"))
    )
    (net (code "79") (name "unconnected-(U4-TEST2-Pad6)") (class "Default")
      (node (ref "U4") (pin "6") (pinfunction "TEST2_6") (pintype "bidirectional"))
    )
    (net (code "80") (name "unconnected-(U4-TEST3-Pad7)") (class "Default")
      (node (ref "U4") (pin "7") (pinfunction "TEST3_7") (pintype "bidirectional"))
    )
    (net (code "81") (name "unconnected-(U4-TEST4-Pad8)") (class "Default")
      (node (ref "U4") (pin "8") (pinfunction "TEST4_8") (pintype "bidirectional"))
    )
    (net (code "82") (name "unconnected-(U4-TEST5-Pad9)") (class "Default")
      (node (ref "U4") (pin "9") (pinfunction "TEST5_9") (pintype "bidirectional"))
    )
    (net (code "83") (name "unconnected-(U4-TEST6-Pad10)") (class "Default")
      (node (ref "U4") (pin "10") (pinfunction "TEST6_10") (pintype "bidirectional"))
    )
  )
)
